# BLE112.net
KiCad netlist of a schematic drawn in Altium Designer
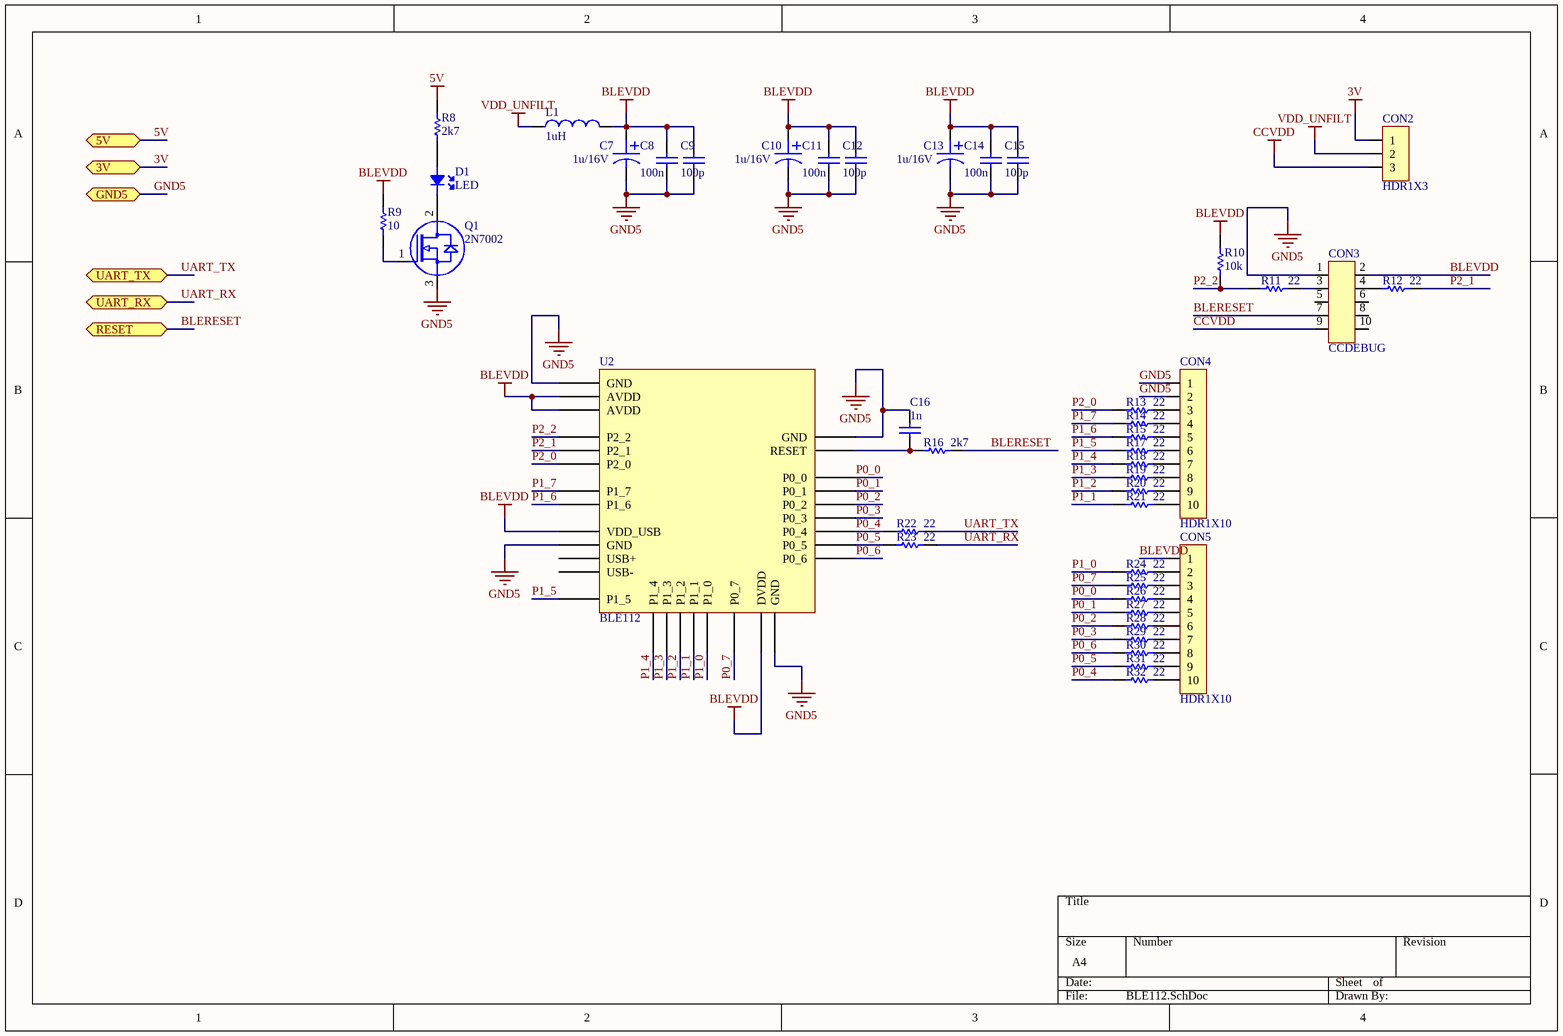
[diagram p0: BLE112.SchDoc]

(export (version "E")
  (design (tool "Eeschema 10.0.6"))
  (components
    (comp (ref "C7")
      (value "1u/16V")
      (footprint "dimploma:CA")
      (libsource (lib "diploma") (part "ELECTROLYTIC_CAPACITOR"))
    )
    (comp (ref "C8")
      (value "100n")
      (footprint "dimploma:0805C")
      (libsource (lib "diploma") (part "CAPACITOR"))
    )
    (comp (ref "C9")
      (value "100p")
      (footprint "dimploma:0805C")
      (libsource (lib "diploma") (part "CAPACITOR"))
    )
    (comp (ref "C10")
      (value "1u/16V")
      (footprint "dimploma:CA")
      (libsource (lib "diploma") (part "ELECTROLYTIC_CAPACITOR"))
    )
    (comp (ref "C11")
      (value "100n")
      (footprint "dimploma:0805C")
      (libsource (lib "diploma") (part "CAPACITOR"))
    )
    (comp (ref "C12")
      (value "100p")
      (footprint "dimploma:0805C")
      (libsource (lib "diploma") (part "CAPACITOR"))
    )
    (comp (ref "C13")
      (value "1u/16V")
      (footprint "dimploma:CA")
      (libsource (lib "diploma") (part "ELECTROLYTIC_CAPACITOR"))
    )
    (comp (ref "C14")
      (value "100n")
      (footprint "dimploma:0805C")
      (libsource (lib "diploma") (part "CAPACITOR"))
    )
    (comp (ref "C15")
      (value "100p")
      (footprint "dimploma:0805C")
      (libsource (lib "diploma") (part "CAPACITOR"))
    )
    (comp (ref "C16")
      (value "1n")
      (footprint "dimploma:0805C")
      (libsource (lib "diploma") (part "CAPACITOR"))
    )
    (comp (ref "CON2")
      (value "HDR1X3")
      (footprint "dimploma:HDR1X3RAST")
      (libsource (lib "diploma") (part "HDR1X3"))
    )
    (comp (ref "CON3")
      (value "CCDEBUG")
      (footprint "dimploma:HDR2X5_CC")
      (libsource (lib "diploma") (part "CCDEBUG"))
    )
    (comp (ref "CON4")
      (value "HDR1X10")
      (footprint "dimploma:HDR1X10RAST")
      (libsource (lib "diploma") (part "HDR1X10"))
    )
    (comp (ref "CON5")
      (value "HDR1X10")
      (footprint "dimploma:HDR1X10RAST")
      (libsource (lib "diploma") (part "HDR1X10"))
    )
    (comp (ref "D1") (value "LED") (footprint "dimploma:0805LED") (libsource (lib "diploma") (part "LED")))
    (comp (ref "L1") (value "1uH") (footprint "dimploma:0805L") (libsource (lib "diploma") (part "Inductor")))
    (comp (ref "Q1")
      (value "2N7002")
      (footprint "dimploma:SOT23")
      (libsource (lib "diploma") (part "2N7002"))
    )
    (comp (ref "R8") (value "2k7") (footprint "dimploma:0805R") (libsource (lib "diploma") (part "RESISTOR")))
    (comp (ref "R9") (value "10") (footprint "dimploma:0805R") (libsource (lib "diploma") (part "RESISTOR")))
    (comp (ref "R10")
      (value "10k")
      (footprint "dimploma:0805R")
      (libsource (lib "diploma") (part "RESISTOR"))
    )
    (comp (ref "R11") (value "22") (footprint "dimploma:0805R") (libsource (lib "diploma") (part "RESISTOR")))
    (comp (ref "R12") (value "22") (footprint "dimploma:0805R") (libsource (lib "diploma") (part "RESISTOR")))
    (comp (ref "R13") (value "22") (footprint "dimploma:0805R") (libsource (lib "diploma") (part "RESISTOR")))
    (comp (ref "R14") (value "22") (footprint "dimploma:0805R") (libsource (lib "diploma") (part "RESISTOR")))
    (comp (ref "R15") (value "22") (footprint "dimploma:0805R") (libsource (lib "diploma") (part "RESISTOR")))
    (comp (ref "R16")
      (value "2k7")
      (footprint "dimploma:0805R")
      (libsource (lib "diploma") (part "RESISTOR"))
    )
    (comp (ref "R17") (value "22") (footprint "dimploma:0805R") (libsource (lib "diploma") (part "RESISTOR")))
    (comp (ref "R18") (value "22") (footprint "dimploma:0805R") (libsource (lib "diploma") (part "RESISTOR")))
    (comp (ref "R19") (value "22") (footprint "dimploma:0805R") (libsource (lib "diploma") (part "RESISTOR")))
    (comp (ref "R20") (value "22") (footprint "dimploma:0805R") (libsource (lib "diploma") (part "RESISTOR")))
    (comp (ref "R21") (value "22") (footprint "dimploma:0805R") (libsource (lib "diploma") (part "RESISTOR")))
    (comp (ref "R22") (value "22") (footprint "dimploma:0805R") (libsource (lib "diploma") (part "RESISTOR")))
    (comp (ref "R23") (value "22") (footprint "dimploma:0805R") (libsource (lib "diploma") (part "RESISTOR")))
    (comp (ref "R24") (value "22") (footprint "dimploma:0805R") (libsource (lib "diploma") (part "RESISTOR")))
    (comp (ref "R25") (value "22") (footprint "dimploma:0805R") (libsource (lib "diploma") (part "RESISTOR")))
    (comp (ref "R26") (value "22") (footprint "dimploma:0805R") (libsource (lib "diploma") (part "RESISTOR")))
    (comp (ref "R27") (value "22") (footprint "dimploma:0805R") (libsource (lib "diploma") (part "RESISTOR")))
    (comp (ref "R28") (value "22") (footprint "dimploma:0805R") (libsource (lib "diploma") (part "RESISTOR")))
    (comp (ref "R29") (value "22") (footprint "dimploma:0805R") (libsource (lib "diploma") (part "RESISTOR")))
    (comp (ref "R30") (value "22") (footprint "dimploma:0805R") (libsource (lib "diploma") (part "RESISTOR")))
    (comp (ref "R31") (value "22") (footprint "dimploma:0805R") (libsource (lib "diploma") (part "RESISTOR")))
    (comp (ref "R32") (value "22") (footprint "dimploma:0805R") (libsource (lib "diploma") (part "RESISTOR")))
    (comp (ref "U2")
      (value "BLE112")
      (footprint "dimploma:BLE112")
      (libsource (lib "diploma") (part "BLE112"))
    )
  )
  (nets
    (net (code "1") (name "/BLERESET") (class "Default")
      (node (ref "CON3") (pin "7") (pinfunction "7_7") (pintype "passive"))
      (node (ref "R16") (pin "1") (pinfunction "1_1") (pintype "passive"))
    )
    (net (code "2") (name "/P0_0") (class "Default")
      (node (ref "R26") (pin "2") (pinfunction "2_2") (pintype "passive"))
      (node (ref "U2") (pin "P0_0") (pinfunction "P0_0_P0_0") (pintype "passive"))
    )
    (net (code "3") (name "/P0_1") (class "Default")
      (node (ref "R27") (pin "2") (pinfunction "2_2") (pintype "passive"))
      (node (ref "U2") (pin "P0_1") (pinfunction "P0_1_P0_1") (pintype "passive"))
    )
    (net (code "4") (name "/P0_2") (class "Default")
      (node (ref "R28") (pin "2") (pinfunction "2_2") (pintype "passive"))
      (node (ref "U2") (pin "P0_2") (pinfunction "P0_2_P0_2") (pintype "passive"))
    )
    (net (code "5") (name "/P0_3") (class "Default")
      (node (ref "R29") (pin "2") (pinfunction "2_2") (pintype "passive"))
      (node (ref "U2") (pin "P0_3") (pinfunction "P0_3_P0_3") (pintype "passive"))
    )
    (net (code "6") (name "/P0_4") (class "Default")
      (node (ref "R22") (pin "2") (pinfunction "2_2") (pintype "passive"))
      (node (ref "R32") (pin "2") (pinfunction "2_2") (pintype "passive"))
      (node (ref "U2") (pin "P0_4") (pinfunction "P0_4_P0_4") (pintype "passive"))
    )
    (net (code "7") (name "/P0_5") (class "Default")
      (node (ref "R23") (pin "2") (pinfunction "2_2") (pintype "passive"))
      (node (ref "R31") (pin "2") (pinfunction "2_2") (pintype "passive"))
      (node (ref "U2") (pin "P0_5") (pinfunction "P0_5_P0_5") (pintype "passive"))
    )
    (net (code "8") (name "/P0_6") (class "Default")
      (node (ref "R30") (pin "2") (pinfunction "2_2") (pintype "passive"))
      (node (ref "U2") (pin "P0_6") (pinfunction "P0_6_P0_6") (pintype "passive"))
    )
    (net (code "9") (name "/P0_7") (class "Default")
      (node (ref "R25") (pin "2") (pinfunction "2_2") (pintype "passive"))
      (node (ref "U2") (pin "P0_7") (pinfunction "P0_7_P0_7") (pintype "passive"))
    )
    (net (code "10") (name "/P1_0") (class "Default")
      (node (ref "R24") (pin "2") (pinfunction "2_2") (pintype "passive"))
      (node (ref "U2") (pin "P1_0") (pinfunction "P1_0_P1_0") (pintype "passive"))
    )
    (net (code "11") (name "/P1_1") (class "Default")
      (node (ref "R21") (pin "2") (pinfunction "2_2") (pintype "passive"))
      (node (ref "U2") (pin "P1_1") (pinfunction "P1_1_P1_1") (pintype "passive"))
    )
    (net (code "12") (name "/P1_2") (class "Default")
      (node (ref "R20") (pin "2") (pinfunction "2_2") (pintype "passive"))
      (node (ref "U2") (pin "P1_2") (pinfunction "P1_2_P1_2") (pintype "passive"))
    )
    (net (code "13") (name "/P1_3") (class "Default")
      (node (ref "R19") (pin "2") (pinfunction "2_2") (pintype "passive"))
      (node (ref "U2") (pin "P1_3") (pinfunction "P1_3_P1_3") (pintype "passive"))
    )
    (net (code "14") (name "/P1_4") (class "Default")
      (node (ref "R18") (pin "2") (pinfunction "2_2") (pintype "passive"))
      (node (ref "U2") (pin "P1_4") (pinfunction "P1_4_P1_4") (pintype "passive"))
    )
    (net (code "15") (name "/P1_5") (class "Default")
      (node (ref "R17") (pin "2") (pinfunction "2_2") (pintype "passive"))
      (node (ref "U2") (pin "P1_5") (pinfunction "P1_5_P1_5") (pintype "passive"))
    )
    (net (code "16") (name "/P1_6") (class "Default")
      (node (ref "R15") (pin "2") (pinfunction "2_2") (pintype "passive"))
      (node (ref "U2") (pin "P1_6") (pinfunction "P1_6_P1_6") (pintype "passive"))
    )
    (net (code "17") (name "/P1_7") (class "Default")
      (node (ref "R14") (pin "2") (pinfunction "2_2") (pintype "passive"))
      (node (ref "U2") (pin "P1_7") (pinfunction "P1_7_P1_7") (pintype "passive"))
    )
    (net (code "18") (name "/P2_0") (class "Default")
      (node (ref "R13") (pin "2") (pinfunction "2_2") (pintype "passive"))
      (node (ref "U2") (pin "P2_0") (pinfunction "P2_0_P2_0") (pintype "passive"))
    )
    (net (code "19") (name "/P2_1") (class "Default")
      (node (ref "R12") (pin "1") (pinfunction "1_1") (pintype "passive"))
      (node (ref "U2") (pin "P2_1") (pinfunction "P2_1_P2_1") (pintype "passive"))
    )
    (net (code "20") (name "/P2_2") (class "Default")
      (node (ref "R10") (pin "2") (pinfunction "2_2") (pintype "passive"))
      (node (ref "R11") (pin "2") (pinfunction "2_2") (pintype "passive"))
      (node (ref "U2") (pin "P2_2") (pinfunction "P2_2_P2_2") (pintype "passive"))
    )
    (net (code "21") (name "/UART_RX") (class "Default")
      (node (ref "R23") (pin "1") (pinfunction "1_1") (pintype "passive"))
    )
    (net (code "22") (name "/UART_TX") (class "Default")
      (node (ref "R22") (pin "1") (pinfunction "1_1") (pintype "passive"))
    )
    (net (code "23") (name "3V") (class "Default")
      (node (ref "CON2") (pin "1") (pinfunction "1_1") (pintype "passive"))
    )
    (net (code "24") (name "5V") (class "Default")
      (node (ref "R8") (pin "2") (pinfunction "2_2") (pintype "passive"))
    )
    (net (code "25") (name "BLEVDD") (class "Default")
      (node (ref "C10") (pin "1") (pinfunction "1_1") (pintype "passive"))
      (node (ref "C11") (pin "2") (pinfunction "2_2") (pintype "passive"))
      (node (ref "C12") (pin "2") (pinfunction "2_2") (pintype "passive"))
      (node (ref "C13") (pin "1") (pinfunction "1_1") (pintype "passive"))
      (node (ref "C14") (pin "2") (pinfunction "2_2") (pintype "passive"))
      (node (ref "C15") (pin "2") (pinfunction "2_2") (pintype "passive"))
      (node (ref "C7") (pin "1") (pinfunction "1_1") (pintype "passive"))
      (node (ref "C8") (pin "2") (pinfunction "2_2") (pintype "passive"))
      (node (ref "C9") (pin "2") (pinfunction "2_2") (pintype "passive"))
      (node (ref "CON3") (pin "2") (pinfunction "2_2") (pintype "passive"))
      (node (ref "CON5") (pin "1") (pinfunction "1_1") (pintype "passive"))
      (node (ref "L1") (pin "2") (pinfunction "2_2") (pintype "passive"))
      (node (ref "R10") (pin "1") (pinfunction "1_1") (pintype "passive"))
      (node (ref "R9") (pin "2") (pinfunction "2_2") (pintype "passive"))
      (node (ref "U2") (pin "AVDD") (pinfunction "AVDD_AVDD") (pintype "passive"))
      (node (ref "U2") (pin "DVDD") (pinfunction "DVDD_DVDD") (pintype "passive"))
      (node (ref "U2") (pin "VDD_USB") (pinfunction "VDD_USB_VDD_USB") (pintype "passive"))
    )
    (net (code "26") (name "CCVDD") (class "Default")
      (node (ref "CON2") (pin "3") (pinfunction "3_3") (pintype "passive"))
      (node (ref "CON3") (pin "9") (pinfunction "9_9") (pintype "passive"))
    )
    (net (code "27") (name "GND5") (class "Default")
      (node (ref "C10") (pin "2") (pinfunction "2_2") (pintype "passive"))
      (node (ref "C11") (pin "1") (pinfunction "1_1") (pintype "passive"))
      (node (ref "C12") (pin "1") (pinfunction "1_1") (pintype "passive"))
      (node (ref "C13") (pin "2") (pinfunction "2_2") (pintype "passive"))
      (node (ref "C14") (pin "1") (pinfunction "1_1") (pintype "passive"))
      (node (ref "C15") (pin "1") (pinfunction "1_1") (pintype "passive"))
      (node (ref "C16") (pin "2") (pinfunction "2_2") (pintype "passive"))
      (node (ref "C7") (pin "2") (pinfunction "2_2") (pintype "passive"))
      (node (ref "C8") (pin "1") (pinfunction "1_1") (pintype "passive"))
      (node (ref "C9") (pin "1") (pinfunction "1_1") (pintype "passive"))
      (node (ref "CON3") (pin "1") (pinfunction "1_1") (pintype "passive"))
      (node (ref "CON4") (pin "1") (pinfunction "1_1") (pintype "passive"))
      (node (ref "CON4") (pin "2") (pinfunction "2_2") (pintype "passive"))
      (node (ref "Q1") (pin "3") (pinfunction "SOURCE_3") (pintype "passive"))
      (node (ref "U2") (pin "GND") (pinfunction "GND_GND") (pintype "passive"))
    )
    (net (code "28") (name "Net-(C16-Pad1)") (class "Default")
      (node (ref "C16") (pin "1") (pinfunction "1_1") (pintype "passive"))
      (node (ref "R16") (pin "2") (pinfunction "2_2") (pintype "passive"))
      (node (ref "U2") (pin "RESET") (pinfunction "RESET_RESET") (pintype "passive"))
    )
    (net (code "29") (name "Net-(CON3-Pad3)") (class "Default")
      (node (ref "CON3") (pin "3") (pinfunction "3_3") (pintype "passive"))
      (node (ref "R11") (pin "1") (pinfunction "1_1") (pintype "passive"))
    )
    (net (code "30") (name "Net-(CON3-Pad4)") (class "Default")
      (node (ref "CON3") (pin "4") (pinfunction "4_4") (pintype "passive"))
      (node (ref "R12") (pin "2") (pinfunction "2_2") (pintype "passive"))
    )
    (net (code "31") (name "Net-(CON4-Pad3)") (class "Default")
      (node (ref "CON4") (pin "3") (pinfunction "3_3") (pintype "passive"))
      (node (ref "R13") (pin "1") (pinfunction "1_1") (pintype "passive"))
    )
    (net (code "32") (name "Net-(CON4-Pad4)") (class "Default")
      (node (ref "CON4") (pin "4") (pinfunction "4_4") (pintype "passive"))
      (node (ref "R14") (pin "1") (pinfunction "1_1") (pintype "passive"))
    )
    (net (code "33") (name "Net-(CON4-Pad5)") (class "Default")
      (node (ref "CON4") (pin "5") (pinfunction "5_5") (pintype "passive"))
      (node (ref "R15") (pin "1") (pinfunction "1_1") (pintype "passive"))
    )
    (net (code "34") (name "Net-(CON4-Pad6)") (class "Default")
      (node (ref "CON4") (pin "6") (pinfunction "6_6") (pintype "passive"))
      (node (ref "R17") (pin "1") (pinfunction "1_1") (pintype "passive"))
    )
    (net (code "35") (name "Net-(CON4-Pad7)") (class "Default")
      (node (ref "CON4") (pin "7") (pinfunction "7_7") (pintype "passive"))
      (node (ref "R18") (pin "1") (pinfunction "1_1") (pintype "passive"))
    )
    (net (code "36") (name "Net-(CON4-Pad8)") (class "Default")
      (node (ref "CON4") (pin "8") (pinfunction "8_8") (pintype "passive"))
      (node (ref "R19") (pin "1") (pinfunction "1_1") (pintype "passive"))
    )
    (net (code "37") (name "Net-(CON4-Pad9)") (class "Default")
      (node (ref "CON4") (pin "9") (pinfunction "9_9") (pintype "passive"))
      (node (ref "R20") (pin "1") (pinfunction "1_1") (pintype "passive"))
    )
    (net (code "38") (name "Net-(CON4-Pad10)") (class "Default")
      (node (ref "CON4") (pin "10") (pinfunction "10_10") (pintype "passive"))
      (node (ref "R21") (pin "1") (pinfunction "1_1") (pintype "passive"))
    )
    (net (code "39") (name "Net-(CON5-Pad2)") (class "Default")
      (node (ref "CON5") (pin "2") (pinfunction "2_2") (pintype "passive"))
      (node (ref "R24") (pin "1") (pinfunction "1_1") (pintype "passive"))
    )
    (net (code "40") (name "Net-(CON5-Pad3)") (class "Default")
      (node (ref "CON5") (pin "3") (pinfunction "3_3") (pintype "passive"))
      (node (ref "R25") (pin "1") (pinfunction "1_1") (pintype "passive"))
    )
    (net (code "41") (name "Net-(CON5-Pad4)") (class "Default")
      (node (ref "CON5") (pin "4") (pinfunction "4_4") (pintype "passive"))
      (node (ref "R26") (pin "1") (pinfunction "1_1") (pintype "passive"))
    )
    (net (code "42") (name "Net-(CON5-Pad5)") (class "Default")
      (node (ref "CON5") (pin "5") (pinfunction "5_5") (pintype "passive"))
      (node (ref "R27") (pin "1") (pinfunction "1_1") (pintype "passive"))
    )
    (net (code "43") (name "Net-(CON5-Pad6)") (class "Default")
      (node (ref "CON5") (pin "6") (pinfunction "6_6") (pintype "passive"))
      (node (ref "R28") (pin "1") (pinfunction "1_1") (pintype "passive"))
    )
    (net (code "44") (name "Net-(CON5-Pad7)") (class "Default")
      (node (ref "CON5") (pin "7") (pinfunction "7_7") (pintype "passive"))
      (node (ref "R29") (pin "1") (pinfunction "1_1") (pintype "passive"))
    )
    (net (code "45") (name "Net-(CON5-Pad8)") (class "Default")
      (node (ref "CON5") (pin "8") (pinfunction "8_8") (pintype "passive"))
      (node (ref "R30") (pin "1") (pinfunction "1_1") (pintype "passive"))
    )
    (net (code "46") (name "Net-(CON5-Pad9)") (class "Default")
      (node (ref "CON5") (pin "9") (pinfunction "9_9") (pintype "passive"))
      (node (ref "R31") (pin "1") (pinfunction "1_1") (pintype "passive"))
    )
    (net (code "47") (name "Net-(CON5-Pad10)") (class "Default")
      (node (ref "CON5") (pin "10") (pinfunction "10_10") (pintype "passive"))
      (node (ref "R32") (pin "1") (pinfunction "1_1") (pintype "passive"))
    )
    (net (code "48") (name "Net-(D1-A)") (class "Default")
      (node (ref "D1") (pin "1") (pinfunction "A_1") (pintype "passive"))
      (node (ref "R8") (pin "1") (pinfunction "1_1") (pintype "passive"))
    )
    (net (code "49") (name "Net-(D1-K)") (class "Default")
      (node (ref "D1") (pin "2") (pinfunction "K_2") (pintype "passive"))
      (node (ref "Q1") (pin "2") (pinfunction "DRAIN_2") (pintype "passive"))
    )
    (net (code "50") (name "Net-(Q1-GATE)") (class "Default")
      (node (ref "Q1") (pin "1") (pinfunction "GATE_1") (pintype "passive"))
      (node (ref "R9") (pin "1") (pinfunction "1_1") (pintype "passive"))
    )
    (net (code "51") (name "VDD_UNFILT") (class "Default")
      (node (ref "CON2") (pin "2") (pinfunction "2_2") (pintype "passive"))
      (node (ref "L1") (pin "1") (pinfunction "1_1") (pintype "passive"))
    )
    (net (code "52") (name "unconnected-(CON3-Pad5)") (class "Default")
      (node (ref "CON3") (pin "5") (pinfunction "5_5") (pintype "passive"))
    )
    (net (code "53") (name "unconnected-(CON3-Pad6)") (class "Default")
      (node (ref "CON3") (pin "6") (pinfunction "6_6") (pintype "passive"))
    )
    (net (code "54") (name "unconnected-(CON3-Pad8)") (class "Default")
      (node (ref "CON3") (pin "8") (pinfunction "8_8") (pintype "passive"))
    )
    (net (code "55") (name "unconnected-(CON3-Pad10)") (class "Default")
      (node (ref "CON3") (pin "10") (pinfunction "10_10") (pintype "passive"))
    )
    (net (code "56") (name "unconnected-(U2-PadUSB+)") (class "Default")
      (node (ref "U2") (pin "USB+") (pinfunction "USB+_USB+") (pintype "passive"))
    )
    (net (code "57") (name "unconnected-(U2-PadUSB-)") (class "Default")
      (node (ref "U2") (pin "USB-") (pinfunction "USB-_USB-") (pintype "passive"))
    )
  )
)
